# light_panel.net
KiCad netlist of a schematic drawn in Altium Designer
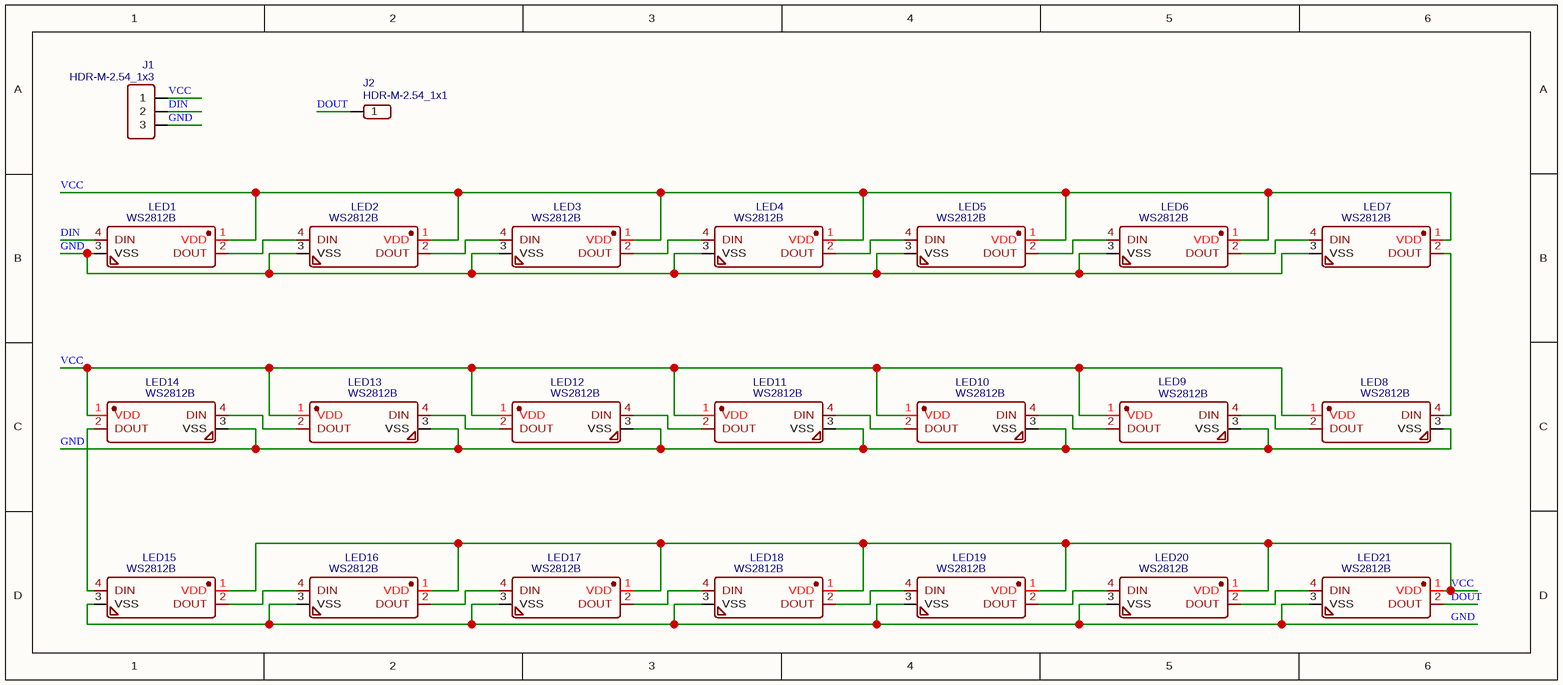
[diagram p0: light_panel.schdoc]

(export (version "E")
  (design (tool "Eeschema 10.0.6"))
  (components
    (comp (ref "J1")
      (value "HDR-M-2.54_1x3")
      (fields (field (name "BOM_SUPPLIER PART") "C180248") (field (name "CONTRIBUTOR") "LCEDA_Lib"))
      (libsource (lib "altium-import") (part "root_0_HDR-M-2.54_1x3_"))
    )
    (comp (ref "J2")
      (value "HDR-M-2.54_1x1")
      (fields (field (name "BOM_SUPPLIER PART") "C81276") (field (name "CONTRIBUTOR") "LCEDA_Lib"))
      (libsource (lib "altium-import") (part "root_0_HDR-M-2.54_1x1_"))
    )
    (comp (ref "LED1")
      (value "WS2812B")
      (fields (field (name "BOM_SUPPLIER PART") "C114585") (field (name "CONTRIBUTOR") "LCSC"))
      (libsource (lib "") (part "root_0_WS2812B__1"))
    )
    (comp (ref "LED2")
      (value "WS2812B")
      (fields (field (name "BOM_SUPPLIER PART") "C114585") (field (name "CONTRIBUTOR") "LCSC"))
      (libsource (lib "") (part "root_0_WS2812B__1"))
    )
    (comp (ref "LED3")
      (value "WS2812B")
      (fields (field (name "BOM_SUPPLIER PART") "C114585") (field (name "CONTRIBUTOR") "LCSC"))
      (libsource (lib "") (part "root_0_WS2812B__1"))
    )
    (comp (ref "LED4")
      (value "WS2812B")
      (fields (field (name "BOM_SUPPLIER PART") "C114585") (field (name "CONTRIBUTOR") "LCSC"))
      (libsource (lib "") (part "root_0_WS2812B__1"))
    )
    (comp (ref "LED5")
      (value "WS2812B")
      (fields (field (name "BOM_SUPPLIER PART") "C114585") (field (name "CONTRIBUTOR") "LCSC"))
      (libsource (lib "") (part "root_0_WS2812B__1"))
    )
    (comp (ref "LED6")
      (value "WS2812B")
      (fields (field (name "BOM_SUPPLIER PART") "C114585") (field (name "CONTRIBUTOR") "LCSC"))
      (libsource (lib "") (part "root_0_WS2812B__1"))
    )
    (comp (ref "LED7")
      (value "WS2812B")
      (fields (field (name "BOM_SUPPLIER PART") "C114585") (field (name "CONTRIBUTOR") "LCSC"))
      (libsource (lib "") (part "root_0_WS2812B__1"))
    )
    (comp (ref "LED8")
      (value "WS2812B")
      (fields (field (name "BOM_SUPPLIER PART") "C114585") (field (name "CONTRIBUTOR") "LCSC"))
      (libsource (lib "altium-import") (part "root_0_WS2812B_"))
    )
    (comp (ref "LED9")
      (value "WS2812B")
      (fields (field (name "BOM_SUPPLIER PART") "C114585") (field (name "CONTRIBUTOR") "LCSC"))
      (libsource (lib "altium-import") (part "root_0_WS2812B_"))
    )
    (comp (ref "LED10")
      (value "WS2812B")
      (fields (field (name "BOM_SUPPLIER PART") "C114585") (field (name "CONTRIBUTOR") "LCSC"))
      (libsource (lib "altium-import") (part "root_0_WS2812B_"))
    )
    (comp (ref "LED11")
      (value "WS2812B")
      (fields (field (name "BOM_SUPPLIER PART") "C114585") (field (name "CONTRIBUTOR") "LCSC"))
      (libsource (lib "altium-import") (part "root_0_WS2812B_"))
    )
    (comp (ref "LED12")
      (value "WS2812B")
      (fields (field (name "BOM_SUPPLIER PART") "C114585") (field (name "CONTRIBUTOR") "LCSC"))
      (libsource (lib "altium-import") (part "root_0_WS2812B_"))
    )
    (comp (ref "LED13")
      (value "WS2812B")
      (fields (field (name "BOM_SUPPLIER PART") "C114585") (field (name "CONTRIBUTOR") "LCSC"))
      (libsource (lib "altium-import") (part "root_0_WS2812B_"))
    )
    (comp (ref "LED14")
      (value "WS2812B")
      (fields (field (name "BOM_SUPPLIER PART") "C114585") (field (name "CONTRIBUTOR") "LCSC"))
      (libsource (lib "altium-import") (part "root_0_WS2812B_"))
    )
    (comp (ref "LED15")
      (value "WS2812B")
      (fields (field (name "BOM_SUPPLIER PART") "C114585") (field (name "CONTRIBUTOR") "LCSC"))
      (libsource (lib "") (part "root_0_WS2812B__1"))
    )
    (comp (ref "LED16")
      (value "WS2812B")
      (fields (field (name "BOM_SUPPLIER PART") "C114585") (field (name "CONTRIBUTOR") "LCSC"))
      (libsource (lib "") (part "root_0_WS2812B__1"))
    )
    (comp (ref "LED17")
      (value "WS2812B")
      (fields (field (name "BOM_SUPPLIER PART") "C114585") (field (name "CONTRIBUTOR") "LCSC"))
      (libsource (lib "") (part "root_0_WS2812B__1"))
    )
    (comp (ref "LED18")
      (value "WS2812B")
      (fields (field (name "BOM_SUPPLIER PART") "C114585") (field (name "CONTRIBUTOR") "LCSC"))
      (libsource (lib "") (part "root_0_WS2812B__1"))
    )
    (comp (ref "LED19")
      (value "WS2812B")
      (fields (field (name "BOM_SUPPLIER PART") "C114585") (field (name "CONTRIBUTOR") "LCSC"))
      (libsource (lib "") (part "root_0_WS2812B__1"))
    )
    (comp (ref "LED20")
      (value "WS2812B")
      (fields (field (name "BOM_SUPPLIER PART") "C114585") (field (name "CONTRIBUTOR") "LCSC"))
      (libsource (lib "") (part "root_0_WS2812B__1"))
    )
    (comp (ref "LED21")
      (value "WS2812B")
      (fields (field (name "BOM_SUPPLIER PART") "C114585") (field (name "CONTRIBUTOR") "LCSC"))
      (libsource (lib "") (part "root_0_WS2812B__1"))
    )
  )
  (nets
    (net (code "1") (name "/DIN") (class "Default")
      (node (ref "J1") (pin "2") (pinfunction "2_2") (pintype "passive"))
      (node (ref "LED1") (pin "4") (pinfunction "DIN_4") (pintype "passive"))
    )
    (net (code "2") (name "/DOUT") (class "Default")
      (node (ref "J2") (pin "1") (pinfunction "1_1") (pintype "passive"))
      (node (ref "LED21") (pin "2") (pinfunction "DOUT_2") (pintype "passive"))
    )
    (net (code "3") (name "/GND") (class "Default")
      (node (ref "J1") (pin "3") (pinfunction "3_3") (pintype "passive"))
      (node (ref "LED1") (pin "3") (pinfunction "VSS_3") (pintype "passive"))
      (node (ref "LED10") (pin "3") (pinfunction "VSS_3") (pintype "passive"))
      (node (ref "LED11") (pin "3") (pinfunction "VSS_3") (pintype "passive"))
      (node (ref "LED12") (pin "3") (pinfunction "VSS_3") (pintype "passive"))
      (node (ref "LED13") (pin "3") (pinfunction "VSS_3") (pintype "passive"))
      (node (ref "LED14") (pin "3") (pinfunction "VSS_3") (pintype "passive"))
      (node (ref "LED15") (pin "3") (pinfunction "VSS_3") (pintype "passive"))
      (node (ref "LED16") (pin "3") (pinfunction "VSS_3") (pintype "passive"))
      (node (ref "LED17") (pin "3") (pinfunction "VSS_3") (pintype "passive"))
      (node (ref "LED18") (pin "3") (pinfunction "VSS_3") (pintype "passive"))
      (node (ref "LED19") (pin "3") (pinfunction "VSS_3") (pintype "passive"))
      (node (ref "LED2") (pin "3") (pinfunction "VSS_3") (pintype "passive"))
      (node (ref "LED20") (pin "3") (pinfunction "VSS_3") (pintype "passive"))
      (node (ref "LED21") (pin "3") (pinfunction "VSS_3") (pintype "passive"))
      (node (ref "LED3") (pin "3") (pinfunction "VSS_3") (pintype "passive"))
      (node (ref "LED4") (pin "3") (pinfunction "VSS_3") (pintype "passive"))
      (node (ref "LED5") (pin "3") (pinfunction "VSS_3") (pintype "passive"))
      (node (ref "LED6") (pin "3") (pinfunction "VSS_3") (pintype "passive"))
      (node (ref "LED7") (pin "3") (pinfunction "VSS_3") (pintype "passive"))
      (node (ref "LED8") (pin "3") (pinfunction "VSS_3") (pintype "passive"))
      (node (ref "LED9") (pin "3") (pinfunction "VSS_3") (pintype "passive"))
    )
    (net (code "4") (name "/VCC") (class "Default")
      (node (ref "J1") (pin "1") (pinfunction "1_1") (pintype "passive"))
      (node (ref "LED1") (pin "1") (pinfunction "VDD_1") (pintype "passive"))
      (node (ref "LED10") (pin "1") (pinfunction "VDD_1") (pintype "passive"))
      (node (ref "LED11") (pin "1") (pinfunction "VDD_1") (pintype "passive"))
      (node (ref "LED12") (pin "1") (pinfunction "VDD_1") (pintype "passive"))
      (node (ref "LED13") (pin "1") (pinfunction "VDD_1") (pintype "passive"))
      (node (ref "LED14") (pin "1") (pinfunction "VDD_1") (pintype "passive"))
      (node (ref "LED15") (pin "1") (pinfunction "VDD_1") (pintype "passive"))
      (node (ref "LED16") (pin "1") (pinfunction "VDD_1") (pintype "passive"))
      (node (ref "LED17") (pin "1") (pinfunction "VDD_1") (pintype "passive"))
      (node (ref "LED18") (pin "1") (pinfunction "VDD_1") (pintype "passive"))
      (node (ref "LED19") (pin "1") (pinfunction "VDD_1") (pintype "passive"))
      (node (ref "LED2") (pin "1") (pinfunction "VDD_1") (pintype "passive"))
      (node (ref "LED20") (pin "1") (pinfunction "VDD_1") (pintype "passive"))
      (node (ref "LED21") (pin "1") (pinfunction "VDD_1") (pintype "passive"))
      (node (ref "LED3") (pin "1") (pinfunction "VDD_1") (pintype "passive"))
      (node (ref "LED4") (pin "1") (pinfunction "VDD_1") (pintype "passive"))
      (node (ref "LED5") (pin "1") (pinfunction "VDD_1") (pintype "passive"))
      (node (ref "LED6") (pin "1") (pinfunction "VDD_1") (pintype "passive"))
      (node (ref "LED7") (pin "1") (pinfunction "VDD_1") (pintype "passive"))
      (node (ref "LED8") (pin "1") (pinfunction "VDD_1") (pintype "passive"))
      (node (ref "LED9") (pin "1") (pinfunction "VDD_1") (pintype "passive"))
    )
    (net (code "5") (name "Net-(LED1-DOUT)") (class "Default")
      (node (ref "LED1") (pin "2") (pinfunction "DOUT_2") (pintype "passive"))
      (node (ref "LED2") (pin "4") (pinfunction "DIN_4") (pintype "passive"))
    )
    (net (code "6") (name "Net-(LED2-DOUT)") (class "Default")
      (node (ref "LED2") (pin "2") (pinfunction "DOUT_2") (pintype "passive"))
      (node (ref "LED3") (pin "4") (pinfunction "DIN_4") (pintype "passive"))
    )
    (net (code "7") (name "Net-(LED3-DOUT)") (class "Default")
      (node (ref "LED3") (pin "2") (pinfunction "DOUT_2") (pintype "passive"))
      (node (ref "LED4") (pin "4") (pinfunction "DIN_4") (pintype "passive"))
    )
    (net (code "8") (name "Net-(LED4-DOUT)") (class "Default")
      (node (ref "LED4") (pin "2") (pinfunction "DOUT_2") (pintype "passive"))
      (node (ref "LED5") (pin "4") (pinfunction "DIN_4") (pintype "passive"))
    )
    (net (code "9") (name "Net-(LED5-DOUT)") (class "Default")
      (node (ref "LED5") (pin "2") (pinfunction "DOUT_2") (pintype "passive"))
      (node (ref "LED6") (pin "4") (pinfunction "DIN_4") (pintype "passive"))
    )
    (net (code "10") (name "Net-(LED6-DOUT)") (class "Default")
      (node (ref "LED6") (pin "2") (pinfunction "DOUT_2") (pintype "passive"))
      (node (ref "LED7") (pin "4") (pinfunction "DIN_4") (pintype "passive"))
    )
    (net (code "11") (name "Net-(LED7-DOUT)") (class "Default")
      (node (ref "LED7") (pin "2") (pinfunction "DOUT_2") (pintype "passive"))
      (node (ref "LED8") (pin "4") (pinfunction "DIN_4") (pintype "passive"))
    )
    (net (code "12") (name "Net-(LED8-DOUT)") (class "Default")
      (node (ref "LED8") (pin "2") (pinfunction "DOUT_2") (pintype "passive"))
      (node (ref "LED9") (pin "4") (pinfunction "DIN_4") (pintype "passive"))
    )
    (net (code "13") (name "Net-(LED10-DIN)") (class "Default")
      (node (ref "LED10") (pin "4") (pinfunction "DIN_4") (pintype "passive"))
      (node (ref "LED9") (pin "2") (pinfunction "DOUT_2") (pintype "passive"))
    )
    (net (code "14") (name "Net-(LED10-DOUT)") (class "Default")
      (node (ref "LED10") (pin "2") (pinfunction "DOUT_2") (pintype "passive"))
      (node (ref "LED11") (pin "4") (pinfunction "DIN_4") (pintype "passive"))
    )
    (net (code "15") (name "Net-(LED11-DOUT)") (class "Default")
      (node (ref "LED11") (pin "2") (pinfunction "DOUT_2") (pintype "passive"))
      (node (ref "LED12") (pin "4") (pinfunction "DIN_4") (pintype "passive"))
    )
    (net (code "16") (name "Net-(LED12-DOUT)") (class "Default")
      (node (ref "LED12") (pin "2") (pinfunction "DOUT_2") (pintype "passive"))
      (node (ref "LED13") (pin "4") (pinfunction "DIN_4") (pintype "passive"))
    )
    (net (code "17") (name "Net-(LED13-DOUT)") (class "Default")
      (node (ref "LED13") (pin "2") (pinfunction "DOUT_2") (pintype "passive"))
      (node (ref "LED14") (pin "4") (pinfunction "DIN_4") (pintype "passive"))
    )
    (net (code "18") (name "Net-(LED14-DOUT)") (class "Default")
      (node (ref "LED14") (pin "2") (pinfunction "DOUT_2") (pintype "passive"))
      (node (ref "LED15") (pin "4") (pinfunction "DIN_4") (pintype "passive"))
    )
    (net (code "19") (name "Net-(LED15-DOUT)") (class "Default")
      (node (ref "LED15") (pin "2") (pinfunction "DOUT_2") (pintype "passive"))
      (node (ref "LED16") (pin "4") (pinfunction "DIN_4") (pintype "passive"))
    )
    (net (code "20") (name "Net-(LED16-DOUT)") (class "Default")
      (node (ref "LED16") (pin "2") (pinfunction "DOUT_2") (pintype "passive"))
      (node (ref "LED17") (pin "4") (pinfunction "DIN_4") (pintype "passive"))
    )
    (net (code "21") (name "Net-(LED17-DOUT)") (class "Default")
      (node (ref "LED17") (pin "2") (pinfunction "DOUT_2") (pintype "passive"))
      (node (ref "LED18") (pin "4") (pinfunction "DIN_4") (pintype "passive"))
    )
    (net (code "22") (name "Net-(LED18-DOUT)") (class "Default")
      (node (ref "LED18") (pin "2") (pinfunction "DOUT_2") (pintype "passive"))
      (node (ref "LED19") (pin "4") (pinfunction "DIN_4") (pintype "passive"))
    )
    (net (code "23") (name "Net-(LED19-DOUT)") (class "Default")
      (node (ref "LED19") (pin "2") (pinfunction "DOUT_2") (pintype "passive"))
      (node (ref "LED20") (pin "4") (pinfunction "DIN_4") (pintype "passive"))
    )
    (net (code "24") (name "Net-(LED20-DOUT)") (class "Default")
      (node (ref "LED20") (pin "2") (pinfunction "DOUT_2") (pintype "passive"))
      (node (ref "LED21") (pin "4") (pinfunction "DIN_4") (pintype "passive"))
    )
  )
)
